# tulip_breakout.net
KiCad netlist of a schematic drawn in EAGLE
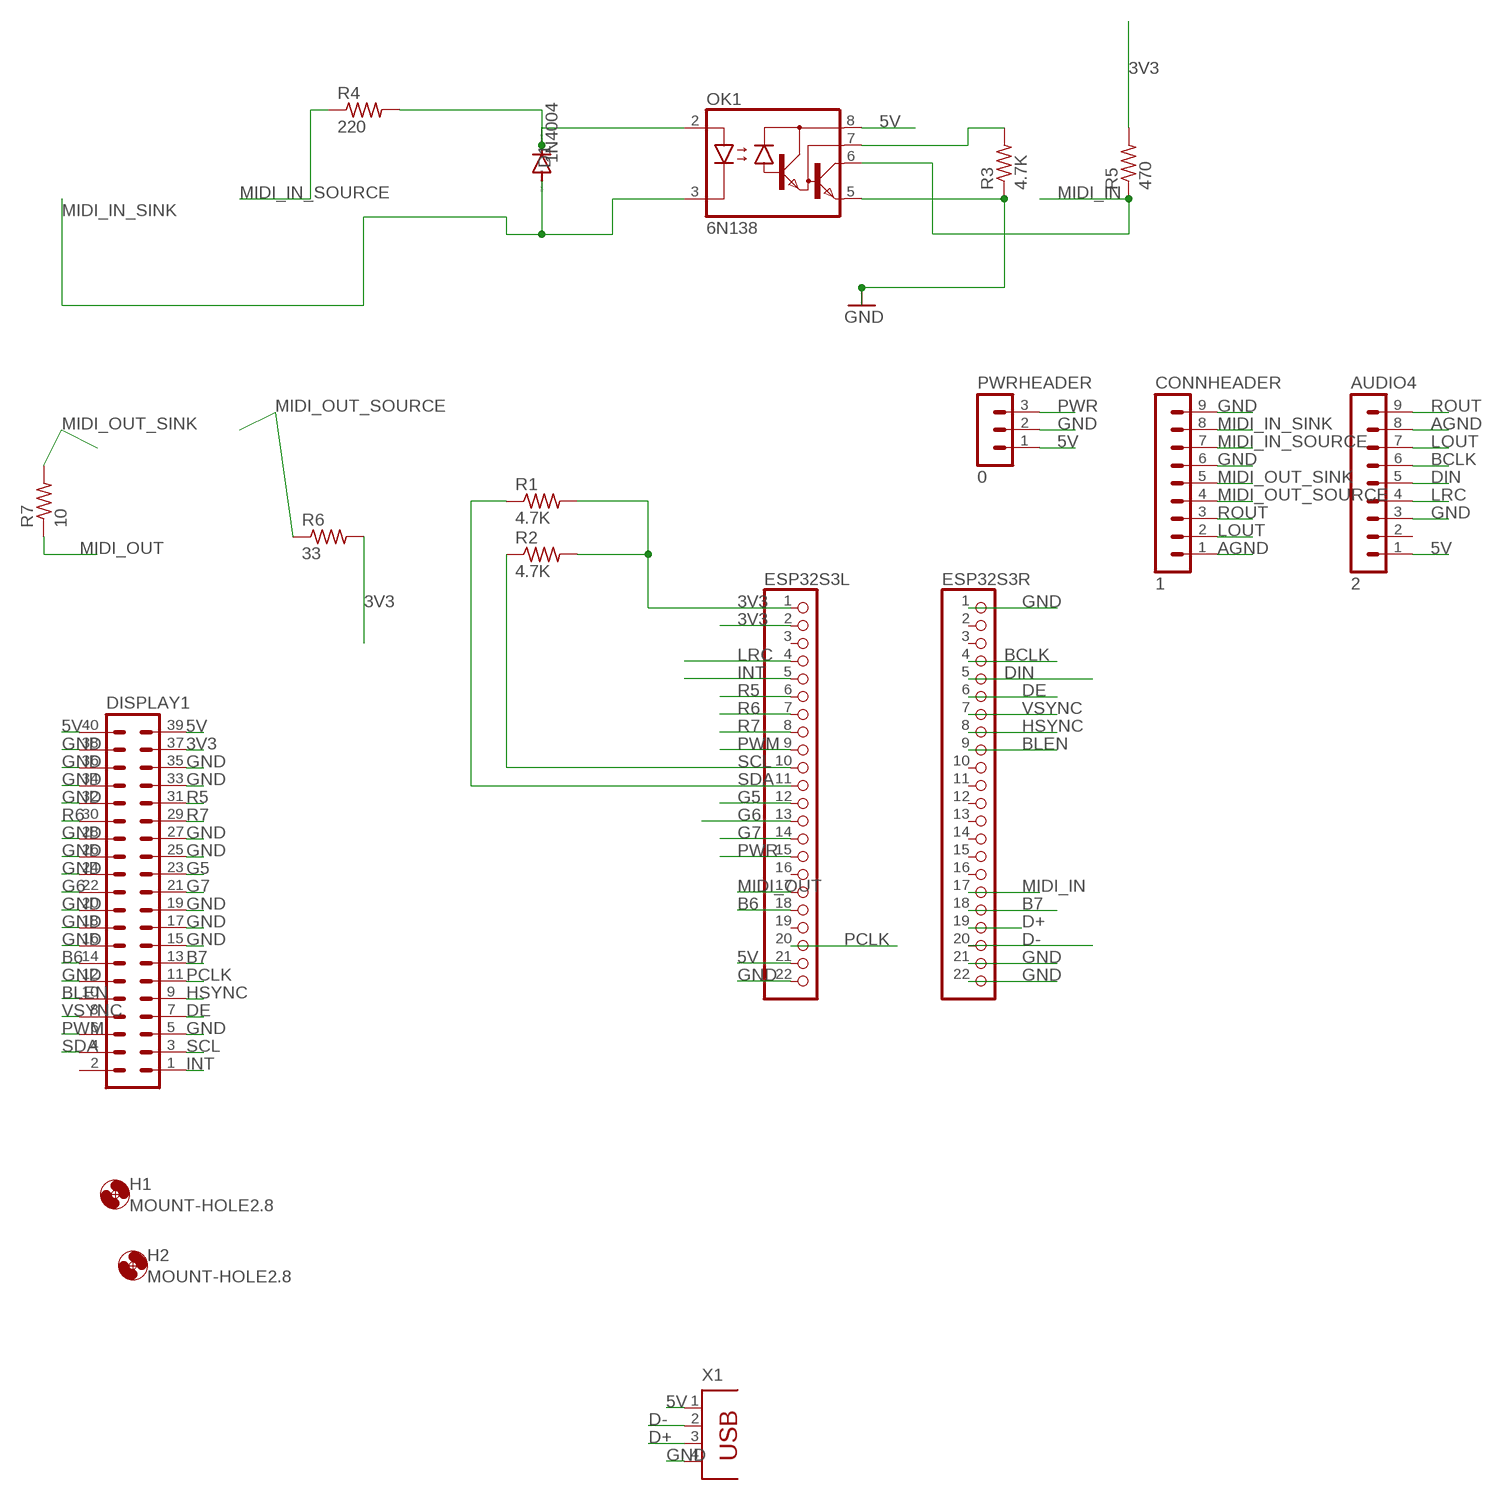
[diagram p0: schematic, sheet 1]

(export (version "E")
  (design (tool "Eeschema 10.0.6"))
  (components
    (comp (ref "AUDIO4")
      (value "2")
      (footprint "eagle-import:MA09-1")
      (libsource (lib "eagle-import") (part "MA09-1"))
    )
    (comp (ref "CONNHEADER")
      (value "1")
      (footprint "eagle-import:MA09-1")
      (libsource (lib "eagle-import") (part "MA09-1"))
    )
    (comp (ref "D1")
      (value "1N4004")
      (footprint "eagle-import:DO41-10")
      (libsource (lib "eagle-import") (part "1N4004"))
    )
    (comp (ref "DISPLAY1")
      (value "MA20-2")
      (footprint "eagle-import:MA20-2")
      (libsource (lib "eagle-import") (part "MA20-2"))
    )
    (comp (ref "ESP32S3L")
      (value "PINHD-1X22")
      (footprint "eagle-import:1X22")
      (libsource (lib "eagle-import") (part "PINHD-1X22"))
    )
    (comp (ref "ESP32S3R")
      (value "PINHD-1X22")
      (footprint "eagle-import:1X22")
      (libsource (lib "eagle-import") (part "PINHD-1X22"))
    )
    (comp (ref "H1")
      (value "MOUNT-HOLE2.8")
      (footprint "eagle-import:2,8")
      (libsource (lib "eagle-import") (part "MOUNT-HOLE2.8"))
    )
    (comp (ref "H2")
      (value "MOUNT-HOLE2.8")
      (footprint "eagle-import:2,8")
      (libsource (lib "eagle-import") (part "MOUNT-HOLE2.8"))
    )
    (comp (ref "OK1")
      (value "6N138")
      (footprint "eagle-import:DIL08")
      (fields (field (name "MF") "VISHAY/TELEFUNKEN"))
      (libsource (lib "eagle-import") (part "6N138"))
    )
    (comp (ref "PWRHEADER")
      (value "0")
      (footprint "eagle-import:MA03-1")
      (libsource (lib "eagle-import") (part "MA03-1"))
    )
    (comp (ref "R1")
      (value "4.7K")
      (footprint "eagle-import:0207_12")
      (libsource (lib "eagle-import") (part "R-US_0207/12"))
    )
    (comp (ref "R2")
      (value "4.7K")
      (footprint "eagle-import:0207_12")
      (libsource (lib "eagle-import") (part "R-US_0207/12"))
    )
    (comp (ref "R3")
      (value "4.7K")
      (footprint "eagle-import:0207_12")
      (libsource (lib "eagle-import") (part "R-US_0207/12"))
    )
    (comp (ref "R4")
      (value "220")
      (footprint "eagle-import:0207_12")
      (libsource (lib "eagle-import") (part "R-US_0207/12"))
    )
    (comp (ref "R5")
      (value "470")
      (footprint "eagle-import:0207_12")
      (libsource (lib "eagle-import") (part "R-US_0207/12"))
    )
    (comp (ref "R6")
      (value "33")
      (footprint "eagle-import:0207_12")
      (libsource (lib "eagle-import") (part "R-US_0207/12"))
    )
    (comp (ref "R7")
      (value "10")
      (footprint "eagle-import:0207_12")
      (libsource (lib "eagle-import") (part "R-US_0207/12"))
    )
    (comp (ref "X1")
      (value "PN87520")
      (footprint "eagle-import:PN87520")
      (libsource (lib "eagle-import") (part "PN87520"))
    )
  )
  (nets
    (net (code "1") (name "/3V3") (class "Default")
      (node (ref "DISPLAY1") (pin "37") (pinfunction "37_37") (pintype "passive"))
      (node (ref "ESP32S3L") (pin "1") (pinfunction "1_1") (pintype "passive"))
      (node (ref "ESP32S3L") (pin "2") (pinfunction "2_2") (pintype "passive"))
      (node (ref "R1") (pin "2") (pinfunction "2_2") (pintype "passive"))
      (node (ref "R2") (pin "2") (pinfunction "2_2") (pintype "passive"))
      (node (ref "R5") (pin "2") (pinfunction "2_2") (pintype "passive"))
      (node (ref "R6") (pin "2") (pinfunction "2_2") (pintype "passive"))
    )
    (net (code "2") (name "/5V") (class "Default")
      (node (ref "AUDIO4") (pin "1") (pinfunction "1_1") (pintype "passive"))
      (node (ref "DISPLAY1") (pin "39") (pinfunction "39_39") (pintype "passive"))
      (node (ref "DISPLAY1") (pin "40") (pinfunction "40_40") (pintype "passive"))
      (node (ref "ESP32S3L") (pin "21") (pinfunction "21_21") (pintype "passive"))
      (node (ref "OK1") (pin "8") (pinfunction "VCC_8") (pintype "passive"))
      (node (ref "PWRHEADER") (pin "1") (pinfunction "1_1") (pintype "passive"))
      (node (ref "X1") (pin "1") (pinfunction "1_1") (pintype "passive"))
    )
    (net (code "3") (name "/AGND") (class "Default")
      (node (ref "AUDIO4") (pin "8") (pinfunction "8_8") (pintype "passive"))
      (node (ref "CONNHEADER") (pin "1") (pinfunction "1_1") (pintype "passive"))
    )
    (net (code "4") (name "/B6") (class "Default")
      (node (ref "DISPLAY1") (pin "14") (pinfunction "14_14") (pintype "passive"))
      (node (ref "ESP32S3L") (pin "18") (pinfunction "18_18") (pintype "passive"))
    )
    (net (code "5") (name "/B7") (class "Default")
      (node (ref "DISPLAY1") (pin "13") (pinfunction "13_13") (pintype "passive"))
      (node (ref "ESP32S3R") (pin "18") (pinfunction "18_18") (pintype "passive"))
    )
    (net (code "6") (name "/BCLK") (class "Default")
      (node (ref "AUDIO4") (pin "6") (pinfunction "6_6") (pintype "passive"))
      (node (ref "ESP32S3R") (pin "4") (pinfunction "4_4") (pintype "passive"))
    )
    (net (code "7") (name "/BLEN") (class "Default")
      (node (ref "DISPLAY1") (pin "10") (pinfunction "10_10") (pintype "passive"))
      (node (ref "ESP32S3R") (pin "9") (pinfunction "9_9") (pintype "passive"))
    )
    (net (code "8") (name "/D+") (class "Default")
      (node (ref "ESP32S3R") (pin "19") (pinfunction "19_19") (pintype "passive"))
      (node (ref "X1") (pin "3") (pinfunction "3_3") (pintype "passive"))
    )
    (net (code "9") (name "/D-") (class "Default")
      (node (ref "ESP32S3R") (pin "20") (pinfunction "20_20") (pintype "passive"))
      (node (ref "X1") (pin "2") (pinfunction "2_2") (pintype "passive"))
    )
    (net (code "10") (name "/DE") (class "Default")
      (node (ref "DISPLAY1") (pin "7") (pinfunction "7_7") (pintype "passive"))
      (node (ref "ESP32S3R") (pin "6") (pinfunction "6_6") (pintype "passive"))
    )
    (net (code "11") (name "/DIN") (class "Default")
      (node (ref "AUDIO4") (pin "5") (pinfunction "5_5") (pintype "passive"))
      (node (ref "ESP32S3R") (pin "5") (pinfunction "5_5") (pintype "passive"))
    )
    (net (code "12") (name "/G5") (class "Default")
      (node (ref "DISPLAY1") (pin "23") (pinfunction "23_23") (pintype "passive"))
      (node (ref "ESP32S3L") (pin "12") (pinfunction "12_12") (pintype "passive"))
    )
    (net (code "13") (name "/G6") (class "Default")
      (node (ref "DISPLAY1") (pin "22") (pinfunction "22_22") (pintype "passive"))
      (node (ref "ESP32S3L") (pin "13") (pinfunction "13_13") (pintype "passive"))
    )
    (net (code "14") (name "/G7") (class "Default")
      (node (ref "DISPLAY1") (pin "21") (pinfunction "21_21") (pintype "passive"))
      (node (ref "ESP32S3L") (pin "14") (pinfunction "14_14") (pintype "passive"))
    )
    (net (code "15") (name "/HSYNC") (class "Default")
      (node (ref "DISPLAY1") (pin "9") (pinfunction "9_9") (pintype "passive"))
      (node (ref "ESP32S3R") (pin "8") (pinfunction "8_8") (pintype "passive"))
    )
    (net (code "16") (name "/INT") (class "Default")
      (node (ref "DISPLAY1") (pin "1") (pinfunction "1_1") (pintype "passive"))
      (node (ref "ESP32S3L") (pin "5") (pinfunction "5_5") (pintype "passive"))
    )
    (net (code "17") (name "/LOUT") (class "Default")
      (node (ref "AUDIO4") (pin "7") (pinfunction "7_7") (pintype "passive"))
      (node (ref "CONNHEADER") (pin "2") (pinfunction "2_2") (pintype "passive"))
    )
    (net (code "18") (name "/LRC") (class "Default")
      (node (ref "AUDIO4") (pin "4") (pinfunction "4_4") (pintype "passive"))
      (node (ref "ESP32S3L") (pin "4") (pinfunction "4_4") (pintype "passive"))
    )
    (net (code "19") (name "/MIDI_IN") (class "Default")
      (node (ref "ESP32S3R") (pin "17") (pinfunction "17_17") (pintype "passive"))
      (node (ref "OK1") (pin "6") (pinfunction "VO_6") (pintype "passive"))
      (node (ref "R5") (pin "1") (pinfunction "1_1") (pintype "passive"))
    )
    (net (code "20") (name "/MIDI_IN_SINK") (class "Default")
      (node (ref "CONNHEADER") (pin "8") (pinfunction "8_8") (pintype "passive"))
      (node (ref "D1") (pin "A") (pinfunction "A_A") (pintype "passive"))
      (node (ref "OK1") (pin "3") (pinfunction "C_3") (pintype "passive"))
    )
    (net (code "21") (name "/MIDI_IN_SOURCE") (class "Default")
      (node (ref "CONNHEADER") (pin "7") (pinfunction "7_7") (pintype "passive"))
      (node (ref "R4") (pin "1") (pinfunction "1_1") (pintype "passive"))
    )
    (net (code "22") (name "/MIDI_OUT") (class "Default")
      (node (ref "ESP32S3L") (pin "17") (pinfunction "17_17") (pintype "passive"))
      (node (ref "R7") (pin "1") (pinfunction "1_1") (pintype "passive"))
    )
    (net (code "23") (name "/MIDI_OUT_SINK") (class "Default")
      (node (ref "CONNHEADER") (pin "5") (pinfunction "5_5") (pintype "passive"))
      (node (ref "R7") (pin "2") (pinfunction "2_2") (pintype "passive"))
    )
    (net (code "24") (name "/MIDI_OUT_SOURCE") (class "Default")
      (node (ref "CONNHEADER") (pin "4") (pinfunction "4_4") (pintype "passive"))
      (node (ref "R6") (pin "1") (pinfunction "1_1") (pintype "passive"))
    )
    (net (code "25") (name "/PCLK") (class "Default")
      (node (ref "DISPLAY1") (pin "11") (pinfunction "11_11") (pintype "passive"))
      (node (ref "ESP32S3L") (pin "20") (pinfunction "20_20") (pintype "passive"))
    )
    (net (code "26") (name "/PWM") (class "Default")
      (node (ref "DISPLAY1") (pin "6") (pinfunction "6_6") (pintype "passive"))
      (node (ref "ESP32S3L") (pin "9") (pinfunction "9_9") (pintype "passive"))
    )
    (net (code "27") (name "/PWR") (class "Default")
      (node (ref "ESP32S3L") (pin "15") (pinfunction "15_15") (pintype "passive"))
      (node (ref "PWRHEADER") (pin "3") (pinfunction "3_3") (pintype "passive"))
    )
    (net (code "28") (name "/R5") (class "Default")
      (node (ref "DISPLAY1") (pin "31") (pinfunction "31_31") (pintype "passive"))
      (node (ref "ESP32S3L") (pin "6") (pinfunction "6_6") (pintype "passive"))
    )
    (net (code "29") (name "/R6") (class "Default")
      (node (ref "DISPLAY1") (pin "30") (pinfunction "30_30") (pintype "passive"))
      (node (ref "ESP32S3L") (pin "7") (pinfunction "7_7") (pintype "passive"))
    )
    (net (code "30") (name "/R7") (class "Default")
      (node (ref "DISPLAY1") (pin "29") (pinfunction "29_29") (pintype "passive"))
      (node (ref "ESP32S3L") (pin "8") (pinfunction "8_8") (pintype "passive"))
    )
    (net (code "31") (name "/ROUT") (class "Default")
      (node (ref "AUDIO4") (pin "9") (pinfunction "9_9") (pintype "passive"))
      (node (ref "CONNHEADER") (pin "3") (pinfunction "3_3") (pintype "passive"))
    )
    (net (code "32") (name "/SCL") (class "Default")
      (node (ref "DISPLAY1") (pin "3") (pinfunction "3_3") (pintype "passive"))
      (node (ref "ESP32S3L") (pin "10") (pinfunction "10_10") (pintype "passive"))
      (node (ref "R2") (pin "1") (pinfunction "1_1") (pintype "passive"))
    )
    (net (code "33") (name "/SDA") (class "Default")
      (node (ref "DISPLAY1") (pin "4") (pinfunction "4_4") (pintype "passive"))
      (node (ref "ESP32S3L") (pin "11") (pinfunction "11_11") (pintype "passive"))
      (node (ref "R1") (pin "1") (pinfunction "1_1") (pintype "passive"))
    )
    (net (code "34") (name "/VSYNC") (class "Default")
      (node (ref "DISPLAY1") (pin "8") (pinfunction "8_8") (pintype "passive"))
      (node (ref "ESP32S3R") (pin "7") (pinfunction "7_7") (pintype "passive"))
    )
    (net (code "35") (name "GND") (class "Default")
      (node (ref "AUDIO4") (pin "3") (pinfunction "3_3") (pintype "passive"))
      (node (ref "CONNHEADER") (pin "6") (pinfunction "6_6") (pintype "passive"))
      (node (ref "CONNHEADER") (pin "9") (pinfunction "9_9") (pintype "passive"))
      (node (ref "DISPLAY1") (pin "12") (pinfunction "12_12") (pintype "passive"))
      (node (ref "DISPLAY1") (pin "15") (pinfunction "15_15") (pintype "passive"))
      (node (ref "DISPLAY1") (pin "16") (pinfunction "16_16") (pintype "passive"))
      (node (ref "DISPLAY1") (pin "17") (pinfunction "17_17") (pintype "passive"))
      (node (ref "DISPLAY1") (pin "18") (pinfunction "18_18") (pintype "passive"))
      (node (ref "DISPLAY1") (pin "19") (pinfunction "19_19") (pintype "passive"))
      (node (ref "DISPLAY1") (pin "20") (pinfunction "20_20") (pintype "passive"))
      (node (ref "DISPLAY1") (pin "24") (pinfunction "24_24") (pintype "passive"))
      (node (ref "DISPLAY1") (pin "25") (pinfunction "25_25") (pintype "passive"))
      (node (ref "DISPLAY1") (pin "26") (pinfunction "26_26") (pintype "passive"))
      (node (ref "DISPLAY1") (pin "27") (pinfunction "27_27") (pintype "passive"))
      (node (ref "DISPLAY1") (pin "28") (pinfunction "28_28") (pintype "passive"))
      (node (ref "DISPLAY1") (pin "32") (pinfunction "32_32") (pintype "passive"))
      (node (ref "DISPLAY1") (pin "33") (pinfunction "33_33") (pintype "passive"))
      (node (ref "DISPLAY1") (pin "34") (pinfunction "34_34") (pintype "passive"))
      (node (ref "DISPLAY1") (pin "35") (pinfunction "35_35") (pintype "passive"))
      (node (ref "DISPLAY1") (pin "36") (pinfunction "36_36") (pintype "passive"))
      (node (ref "DISPLAY1") (pin "38") (pinfunction "38_38") (pintype "passive"))
      (node (ref "DISPLAY1") (pin "5") (pinfunction "5_5") (pintype "passive"))
      (node (ref "ESP32S3L") (pin "22") (pinfunction "22_22") (pintype "passive"))
      (node (ref "ESP32S3R") (pin "1") (pinfunction "1_1") (pintype "passive"))
      (node (ref "ESP32S3R") (pin "21") (pinfunction "21_21") (pintype "passive"))
      (node (ref "ESP32S3R") (pin "22") (pinfunction "22_22") (pintype "passive"))
      (node (ref "OK1") (pin "5") (pinfunction "GND_5") (pintype "passive"))
      (node (ref "PWRHEADER") (pin "2") (pinfunction "2_2") (pintype "passive"))
      (node (ref "R3") (pin "1") (pinfunction "1_1") (pintype "passive"))
      (node (ref "X1") (pin "4") (pinfunction "4_4") (pintype "passive"))
    )
    (net (code "36") (name "Net-(OK1-A)") (class "Default")
      (node (ref "D1") (pin "C") (pinfunction "C_C") (pintype "passive"))
      (node (ref "OK1") (pin "2") (pinfunction "A_2") (pintype "passive"))
      (node (ref "R4") (pin "2") (pinfunction "2_2") (pintype "passive"))
    )
    (net (code "37") (name "Net-(OK1-VB)") (class "Default")
      (node (ref "OK1") (pin "7") (pinfunction "VB_7") (pintype "passive"))
      (node (ref "R3") (pin "2") (pinfunction "2_2") (pintype "passive"))
    )
    (net (code "38") (name "unconnected-(AUDIO4-Pad2)") (class "Default")
      (node (ref "AUDIO4") (pin "2") (pinfunction "2_2") (pintype "passive"))
    )
    (net (code "39") (name "unconnected-(DISPLAY1-Pad2)") (class "Default")
      (node (ref "DISPLAY1") (pin "2") (pinfunction "2_2") (pintype "passive"))
    )
    (net (code "40") (name "unconnected-(ESP32S3L-Pad3)") (class "Default")
      (node (ref "ESP32S3L") (pin "3") (pinfunction "3_3") (pintype "passive"))
    )
    (net (code "41") (name "unconnected-(ESP32S3L-Pad16)") (class "Default")
      (node (ref "ESP32S3L") (pin "16") (pinfunction "16_16") (pintype "passive"))
    )
    (net (code "42") (name "unconnected-(ESP32S3L-Pad19)") (class "Default")
      (node (ref "ESP32S3L") (pin "19") (pinfunction "19_19") (pintype "passive"))
    )
    (net (code "43") (name "unconnected-(ESP32S3R-Pad2)") (class "Default")
      (node (ref "ESP32S3R") (pin "2") (pinfunction "2_2") (pintype "passive"))
    )
    (net (code "44") (name "unconnected-(ESP32S3R-Pad3)") (class "Default")
      (node (ref "ESP32S3R") (pin "3") (pinfunction "3_3") (pintype "passive"))
    )
    (net (code "45") (name "unconnected-(ESP32S3R-Pad10)") (class "Default")
      (node (ref "ESP32S3R") (pin "10") (pinfunction "10_10") (pintype "passive"))
    )
    (net (code "46") (name "unconnected-(ESP32S3R-Pad11)") (class "Default")
      (node (ref "ESP32S3R") (pin "11") (pinfunction "11_11") (pintype "passive"))
    )
    (net (code "47") (name "unconnected-(ESP32S3R-Pad12)") (class "Default")
      (node (ref "ESP32S3R") (pin "12") (pinfunction "12_12") (pintype "passive"))
    )
    (net (code "48") (name "unconnected-(ESP32S3R-Pad13)") (class "Default")
      (node (ref "ESP32S3R") (pin "13") (pinfunction "13_13") (pintype "passive"))
    )
    (net (code "49") (name "unconnected-(ESP32S3R-Pad14)") (class "Default")
      (node (ref "ESP32S3R") (pin "14") (pinfunction "14_14") (pintype "passive"))
    )
    (net (code "50") (name "unconnected-(ESP32S3R-Pad15)") (class "Default")
      (node (ref "ESP32S3R") (pin "15") (pinfunction "15_15") (pintype "passive"))
    )
    (net (code "51") (name "unconnected-(ESP32S3R-Pad16)") (class "Default")
      (node (ref "ESP32S3R") (pin "16") (pinfunction "16_16") (pintype "passive"))
    )
  )
)
